# powerSupply.net
KiCad netlist of a schematic drawn in EAGLE
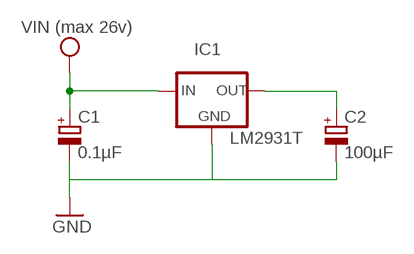
[diagram p0: schematic, sheet 1]

(export (version "E")
  (design (tool "Eeschema 10.0.6"))
  (components
    (comp (ref "C1")
      (value "0.1µF")
      (footprint "eagle-import:E5-5")
      (libsource (lib "eagle-import") (part "CPOL-EUE5-5"))
    )
    (comp (ref "C2")
      (value "100µF")
      (footprint "eagle-import:E5-5")
      (libsource (lib "eagle-import") (part "CPOL-EUE5-5"))
    )
    (comp (ref "IC1")
      (value "LM2931T")
      (footprint "eagle-import:TO220S")
      (libsource (lib "eagle-import") (part "LM2931T"))
    )
  )
  (nets
    (net (code "1") (name "GND") (class "Default")
      (node (ref "C1") (pin "-") (pinfunction "-_-") (pintype "passive"))
      (node (ref "C2") (pin "-") (pinfunction "-_-") (pintype "passive"))
      (node (ref "IC1") (pin "2") (pinfunction "GND_2") (pintype "input"))
    )
    (net (code "2") (name "Net-(IC1-OUT)") (class "Default")
      (node (ref "C2") (pin "+") (pinfunction "+_+") (pintype "passive"))
      (node (ref "IC1") (pin "3") (pinfunction "OUT_3") (pintype "passive"))
    )
    (net (code "3") (name "VIN (max 26v)") (class "Default")
      (node (ref "C1") (pin "+") (pinfunction "+_+") (pintype "passive"))
      (node (ref "IC1") (pin "1") (pinfunction "IN_1") (pintype "input"))
    )
  )
)
